# sms_gw.net
KiCad netlist of a schematic drawn in EAGLE
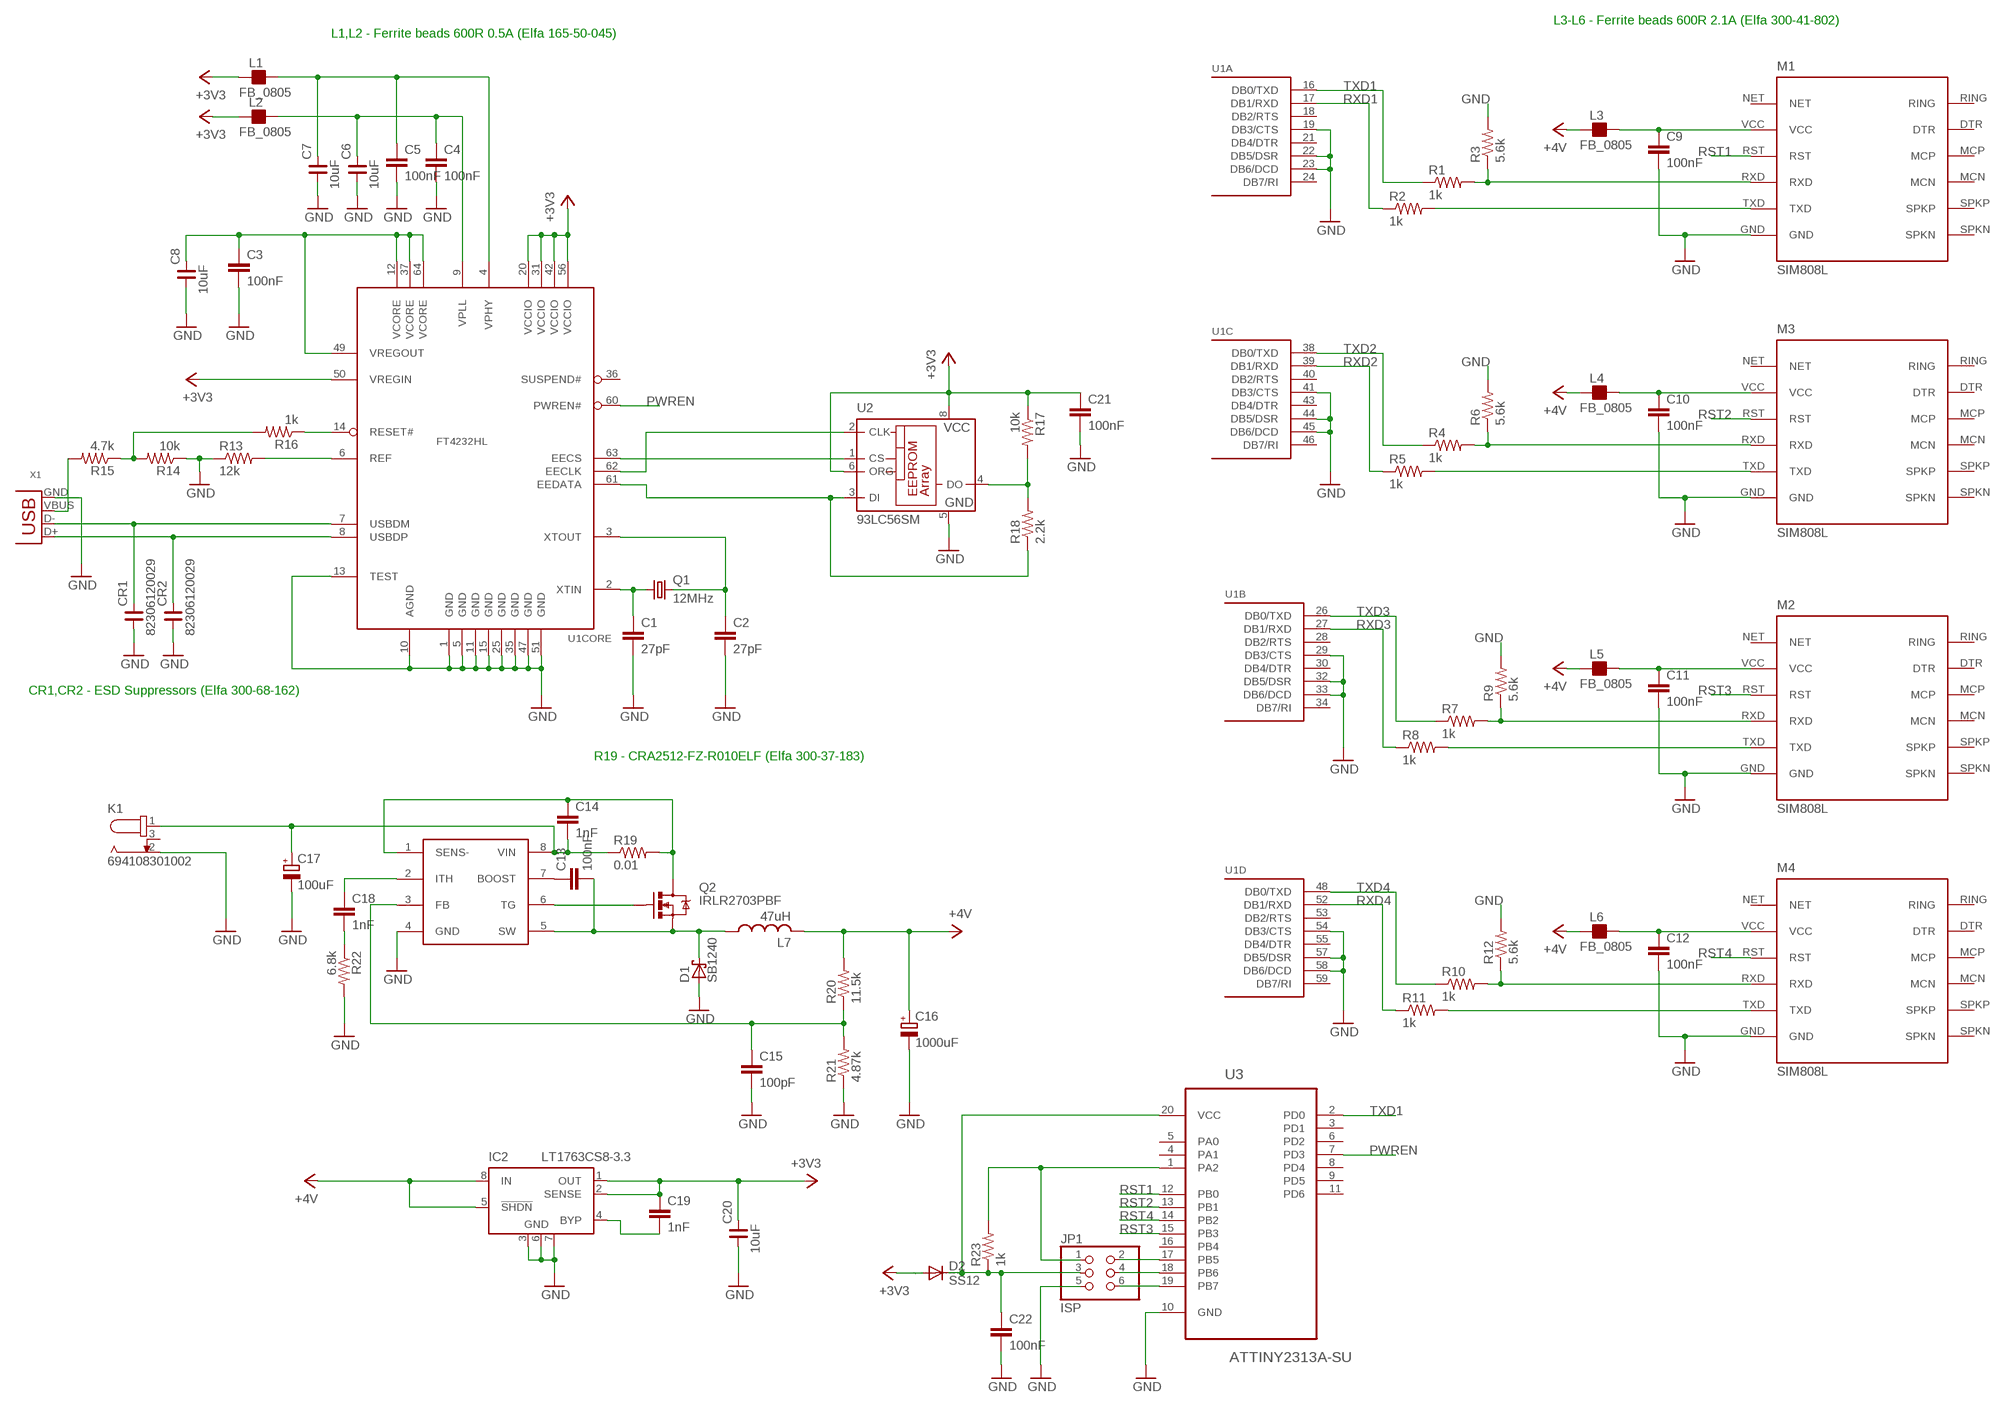
[diagram p0: schematic, sheet 1]

(export (version "E")
  (design (tool "Eeschema 10.0.6"))
  (components
    (comp (ref "C1")
      (value "27pF")
      (footprint "eagle-import:C0805")
      (libsource (lib "eagle-import") (part "C-EUC0805"))
    )
    (comp (ref "C2")
      (value "27pF")
      (footprint "eagle-import:C0805")
      (libsource (lib "eagle-import") (part "C-EUC0805"))
    )
    (comp (ref "C3")
      (value "100nF")
      (footprint "eagle-import:C0805")
      (libsource (lib "eagle-import") (part "C-EUC0805"))
    )
    (comp (ref "C4")
      (value "100nF")
      (footprint "eagle-import:C0805")
      (libsource (lib "eagle-import") (part "C-EUC0805"))
    )
    (comp (ref "C5")
      (value "100nF")
      (footprint "eagle-import:C0805")
      (libsource (lib "eagle-import") (part "C-EUC0805"))
    )
    (comp (ref "C6")
      (value "10uF")
      (footprint "eagle-import:C1210")
      (libsource (lib "eagle-import") (part "C_1210"))
    )
    (comp (ref "C7")
      (value "10uF")
      (footprint "eagle-import:C1210")
      (libsource (lib "eagle-import") (part "C_1210"))
    )
    (comp (ref "C8")
      (value "10uF")
      (footprint "eagle-import:C1210")
      (libsource (lib "eagle-import") (part "C_1210"))
    )
    (comp (ref "C9")
      (value "100nF")
      (footprint "eagle-import:C0805")
      (libsource (lib "eagle-import") (part "C-EUC0805"))
    )
    (comp (ref "C10")
      (value "100nF")
      (footprint "eagle-import:C0805")
      (libsource (lib "eagle-import") (part "C-EUC0805"))
    )
    (comp (ref "C11")
      (value "100nF")
      (footprint "eagle-import:C0805")
      (libsource (lib "eagle-import") (part "C-EUC0805"))
    )
    (comp (ref "C12")
      (value "100nF")
      (footprint "eagle-import:C0805")
      (libsource (lib "eagle-import") (part "C-EUC0805"))
    )
    (comp (ref "C13")
      (value "100nF")
      (footprint "eagle-import:C1206")
      (libsource (lib "eagle-import") (part "C-EUC1206"))
    )
    (comp (ref "C14")
      (value "1nF")
      (footprint "eagle-import:C0805")
      (libsource (lib "eagle-import") (part "C-EUC0805"))
    )
    (comp (ref "C15")
      (value "100pF")
      (footprint "eagle-import:C0805")
      (libsource (lib "eagle-import") (part "C-EUC0805"))
    )
    (comp (ref "C16")
      (value "1000uF")
      (footprint "eagle-import:E5-8,5")
      (libsource (lib "eagle-import") (part "CPOL-EUE5-8.5"))
    )
    (comp (ref "C17")
      (value "100uF")
      (footprint "eagle-import:E5-8,5")
      (libsource (lib "eagle-import") (part "CPOL-EUE5-8.5"))
    )
    (comp (ref "C18")
      (value "1nF")
      (footprint "eagle-import:C0805")
      (libsource (lib "eagle-import") (part "C-EUC0805"))
    )
    (comp (ref "C19")
      (value "1nF")
      (footprint "eagle-import:C0805")
      (libsource (lib "eagle-import") (part "C-EUC0805"))
    )
    (comp (ref "C20")
      (value "10uF")
      (footprint "eagle-import:C1210")
      (libsource (lib "eagle-import") (part "C_1210"))
    )
    (comp (ref "C21")
      (value "100nF")
      (footprint "eagle-import:C0805")
      (libsource (lib "eagle-import") (part "C-EUC0805"))
    )
    (comp (ref "C22")
      (value "100nF")
      (footprint "eagle-import:C0805")
      (libsource (lib "eagle-import") (part "C-EUC0805"))
    )
    (comp (ref "CR1")
      (value "82306120029")
      (footprint "eagle-import:C0603")
      (libsource (lib "eagle-import") (part "C_0603"))
    )
    (comp (ref "CR2")
      (value "82306120029")
      (footprint "eagle-import:C0603")
      (libsource (lib "eagle-import") (part "C_0603"))
    )
    (comp (ref "D1")
      (value "SB1240")
      (footprint "eagle-import:F126Z12")
      (libsource (lib "eagle-import") (part "SCHOTTKY-DIODEF126Z12"))
    )
    (comp (ref "D2")
      (value "SS12")
      (footprint "eagle-import:DO-214AC")
      (libsource (lib "eagle-import") (part "DIODE-DO-214AC"))
    )
    (comp (ref "IC1")
      (value "LTC1624S8")
      (footprint "eagle-import:SO08")
      (libsource (lib "eagle-import") (part "LTC1624S8"))
    )
    (comp (ref "IC2")
      (value "LT1763CS8-3.3")
      (footprint "eagle-import:SOIC8")
      (libsource (lib "eagle-import") (part "LT1763CS8-3.3"))
    )
    (comp (ref "JP1")
      (value "ISP")
      (footprint "eagle-import:2X03")
      (libsource (lib "eagle-import") (part "PINHD-2X3"))
    )
    (comp (ref "K1")
      (value "694108301002")
      (footprint "eagle-import:694108301002")
      (libsource (lib "eagle-import") (part "694108301002"))
    )
    (comp (ref "L1")
      (value "FB_0805")
      (footprint "eagle-import:L0805")
      (libsource (lib "eagle-import") (part "FB_0805"))
    )
    (comp (ref "L2")
      (value "FB_0805")
      (footprint "eagle-import:L0805")
      (libsource (lib "eagle-import") (part "FB_0805"))
    )
    (comp (ref "L3")
      (value "FB_0805")
      (footprint "eagle-import:L0805")
      (libsource (lib "eagle-import") (part "FB_0805"))
    )
    (comp (ref "L4")
      (value "FB_0805")
      (footprint "eagle-import:L0805")
      (libsource (lib "eagle-import") (part "FB_0805"))
    )
    (comp (ref "L5")
      (value "FB_0805")
      (footprint "eagle-import:L0805")
      (libsource (lib "eagle-import") (part "FB_0805"))
    )
    (comp (ref "L6")
      (value "FB_0805")
      (footprint "eagle-import:L0805")
      (libsource (lib "eagle-import") (part "FB_0805"))
    )
    (comp (ref "L7")
      (value "47uH")
      (footprint "eagle-import:TJ3-U2")
      (libsource (lib "eagle-import") (part "L-USTJ3-U2"))
    )
    (comp (ref "M1")
      (value "SIM808L")
      (footprint "eagle-import:SIM800L")
      (libsource (lib "eagle-import") (part "SIM808L"))
    )
    (comp (ref "M2")
      (value "SIM808L")
      (footprint "eagle-import:SIM800L")
      (libsource (lib "eagle-import") (part "SIM808L"))
    )
    (comp (ref "M3")
      (value "SIM808L")
      (footprint "eagle-import:SIM800L")
      (libsource (lib "eagle-import") (part "SIM808L"))
    )
    (comp (ref "M4")
      (value "SIM808L")
      (footprint "eagle-import:SIM800L")
      (libsource (lib "eagle-import") (part "SIM808L"))
    )
    (comp (ref "Q1")
      (value "12MHz")
      (footprint "eagle-import:HC49U-V")
      (libsource (lib "eagle-import") (part "CRYSTALHC49U-V"))
    )
    (comp (ref "Q2")
      (value "IRLR2703PBF")
      (footprint "eagle-import:DPAK")
      (libsource (lib "eagle-import") (part "MOSFET-NCHANNELFDD8780"))
    )
    (comp (ref "R1")
      (value "1k")
      (footprint "eagle-import:R0805")
      (libsource (lib "eagle-import") (part "R-US_R0805"))
    )
    (comp (ref "R2")
      (value "1k")
      (footprint "eagle-import:R0805")
      (libsource (lib "eagle-import") (part "R-US_R0805"))
    )
    (comp (ref "R3")
      (value "5.6k")
      (footprint "eagle-import:R0805")
      (libsource (lib "eagle-import") (part "R-US_R0805"))
    )
    (comp (ref "R4")
      (value "1k")
      (footprint "eagle-import:R0805")
      (libsource (lib "eagle-import") (part "R-US_R0805"))
    )
    (comp (ref "R5")
      (value "1k")
      (footprint "eagle-import:R0805")
      (libsource (lib "eagle-import") (part "R-US_R0805"))
    )
    (comp (ref "R6")
      (value "5.6k")
      (footprint "eagle-import:R0805")
      (libsource (lib "eagle-import") (part "R-US_R0805"))
    )
    (comp (ref "R7")
      (value "1k")
      (footprint "eagle-import:R0805")
      (libsource (lib "eagle-import") (part "R-US_R0805"))
    )
    (comp (ref "R8")
      (value "1k")
      (footprint "eagle-import:R0805")
      (libsource (lib "eagle-import") (part "R-US_R0805"))
    )
    (comp (ref "R9")
      (value "5.6k")
      (footprint "eagle-import:R0805")
      (libsource (lib "eagle-import") (part "R-US_R0805"))
    )
    (comp (ref "R10")
      (value "1k")
      (footprint "eagle-import:R0805")
      (libsource (lib "eagle-import") (part "R-US_R0805"))
    )
    (comp (ref "R11")
      (value "1k")
      (footprint "eagle-import:R0805")
      (libsource (lib "eagle-import") (part "R-US_R0805"))
    )
    (comp (ref "R12")
      (value "5.6k")
      (footprint "eagle-import:R0805")
      (libsource (lib "eagle-import") (part "R-US_R0805"))
    )
    (comp (ref "R13")
      (value "12k")
      (footprint "eagle-import:R0805")
      (libsource (lib "eagle-import") (part "R-US_R0805"))
    )
    (comp (ref "R14")
      (value "10k")
      (footprint "eagle-import:R0805")
      (libsource (lib "eagle-import") (part "R-US_R0805"))
    )
    (comp (ref "R15")
      (value "4.7k")
      (footprint "eagle-import:R0805")
      (libsource (lib "eagle-import") (part "R-US_R0805"))
    )
    (comp (ref "R16")
      (value "1k")
      (footprint "eagle-import:R0805")
      (libsource (lib "eagle-import") (part "R-US_R0805"))
    )
    (comp (ref "R17")
      (value "10k")
      (footprint "eagle-import:R0805")
      (libsource (lib "eagle-import") (part "R-US_R0805"))
    )
    (comp (ref "R18")
      (value "2.2k")
      (footprint "eagle-import:R0805")
      (libsource (lib "eagle-import") (part "R-US_R0805"))
    )
    (comp (ref "R19")
      (value "0.01")
      (footprint "eagle-import:R2512")
      (libsource (lib "eagle-import") (part "R-US_R2512"))
    )
    (comp (ref "R20")
      (value "11.5k")
      (footprint "eagle-import:R0603")
      (libsource (lib "eagle-import") (part "R-US_R0603"))
    )
    (comp (ref "R21")
      (value "4.87k")
      (footprint "eagle-import:R0603")
      (libsource (lib "eagle-import") (part "R-US_R0603"))
    )
    (comp (ref "R22")
      (value "6.8k")
      (footprint "eagle-import:R0805")
      (libsource (lib "eagle-import") (part "R-US_R0805"))
    )
    (comp (ref "R23")
      (value "1k")
      (footprint "eagle-import:R0805")
      (libsource (lib "eagle-import") (part "R-US_R0805"))
    )
    (comp (ref "U1")
      (value "FT4232HL")
      (footprint "eagle-import:LQFP64")
      (libsource (lib "eagle-import") (part "FT4232HL"))
    )
    (comp (ref "U2")
      (value "93LC56SM")
      (footprint "eagle-import:SO-08M")
      (fields (field (name "MF") "MICROCHIP") (field (name "MPN") "93LC56T/SN"))
      (libsource (lib "eagle-import") (part "93SMLC56"))
    )
    (comp (ref "U3")
      (value "ATTINY2313A-SU")
      (footprint "eagle-import:SOIC127P1032X265-20N")
      (libsource (lib "eagle-import") (part "ATTINY2313A-SU"))
    )
    (comp (ref "X1")
      (value "USB-B-H")
      (footprint "eagle-import:USB-B-H")
      (libsource (lib "eagle-import") (part "USB-B-H"))
    )
  )
  (nets
    (net (code "1") (name "+3V3") (class "Default")
      (node (ref "C19") (pin "1") (pinfunction "1_1") (pintype "passive"))
      (node (ref "C20") (pin "2") (pinfunction "2_2") (pintype "passive"))
      (node (ref "C21") (pin "1") (pinfunction "1_1") (pintype "passive"))
      (node (ref "D2") (pin "A") (pinfunction "A_A") (pintype "passive"))
      (node (ref "IC2") (pin "1") (pinfunction "OUT_1") (pintype "passive"))
      (node (ref "IC2") (pin "2") (pinfunction "SENSE_2") (pintype "input"))
      (node (ref "L1") (pin "1") (pinfunction "1_1") (pintype "passive"))
      (node (ref "L2") (pin "1") (pinfunction "1_1") (pintype "passive"))
      (node (ref "R17") (pin "1") (pinfunction "1_1") (pintype "passive"))
      (node (ref "U1") (pin "20") (pinfunction "VCCIO_20") (pintype "power_in"))
      (node (ref "U1") (pin "31") (pinfunction "VCCIO_31") (pintype "power_in"))
      (node (ref "U1") (pin "42") (pinfunction "VCCIO_42") (pintype "power_in"))
      (node (ref "U1") (pin "50") (pinfunction "VREGIN_50") (pintype "bidirectional"))
      (node (ref "U1") (pin "56") (pinfunction "VCCIO_56") (pintype "power_in"))
      (node (ref "U2") (pin "6") (pinfunction "ORG_6") (pintype "input"))
      (node (ref "U2") (pin "8") (pinfunction "VCC_8") (pintype "power_in"))
    )
    (net (code "2") (name "+4V") (class "Default")
      (node (ref "C16") (pin "+") (pinfunction "+_+") (pintype "passive"))
      (node (ref "IC2") (pin "5") (pinfunction "~{SHDN}_5") (pintype "input"))
      (node (ref "IC2") (pin "8") (pinfunction "IN_8") (pintype "input"))
      (node (ref "L3") (pin "1") (pinfunction "1_1") (pintype "passive"))
      (node (ref "L4") (pin "1") (pinfunction "1_1") (pintype "passive"))
      (node (ref "L5") (pin "1") (pinfunction "1_1") (pintype "passive"))
      (node (ref "L6") (pin "1") (pinfunction "1_1") (pintype "passive"))
      (node (ref "L7") (pin "2") (pinfunction "2_2") (pintype "passive"))
      (node (ref "R20") (pin "2") (pinfunction "2_2") (pintype "passive"))
    )
    (net (code "3") (name "/PWREN") (class "Default")
      (node (ref "U1") (pin "60") (pinfunction "PWREN#_60") (pintype "output"))
      (node (ref "U3") (pin "7") (pinfunction "PD3_7") (pintype "bidirectional"))
    )
    (net (code "4") (name "/RST1") (class "Default")
      (node (ref "M1") (pin "RST") (pinfunction "RST_RST") (pintype "bidirectional"))
      (node (ref "U3") (pin "12") (pinfunction "PB0_12") (pintype "bidirectional"))
    )
    (net (code "5") (name "/RST2") (class "Default")
      (node (ref "M3") (pin "RST") (pinfunction "RST_RST") (pintype "bidirectional"))
      (node (ref "U3") (pin "13") (pinfunction "PB1_13") (pintype "bidirectional"))
    )
    (net (code "6") (name "/RST3") (class "Default")
      (node (ref "M2") (pin "RST") (pinfunction "RST_RST") (pintype "bidirectional"))
      (node (ref "U3") (pin "15") (pinfunction "PB3_15") (pintype "bidirectional"))
    )
    (net (code "7") (name "/RST4") (class "Default")
      (node (ref "M4") (pin "RST") (pinfunction "RST_RST") (pintype "bidirectional"))
      (node (ref "U3") (pin "14") (pinfunction "PB2_14") (pintype "bidirectional"))
    )
    (net (code "8") (name "/RXD1") (class "Default")
      (node (ref "R2") (pin "1") (pinfunction "1_1") (pintype "passive"))
      (node (ref "U1") (pin "17") (pinfunction "DB1/RXD_17") (pintype "bidirectional"))
    )
    (net (code "9") (name "/RXD2") (class "Default")
      (node (ref "R5") (pin "1") (pinfunction "1_1") (pintype "passive"))
      (node (ref "U1") (pin "39") (pinfunction "DB1/RXD_39") (pintype "bidirectional"))
    )
    (net (code "10") (name "/RXD3") (class "Default")
      (node (ref "R8") (pin "1") (pinfunction "1_1") (pintype "passive"))
      (node (ref "U1") (pin "27") (pinfunction "DB1/RXD_27") (pintype "bidirectional"))
    )
    (net (code "11") (name "/RXD4") (class "Default")
      (node (ref "R11") (pin "1") (pinfunction "1_1") (pintype "passive"))
      (node (ref "U1") (pin "52") (pinfunction "DB1/RXD_52") (pintype "bidirectional"))
    )
    (net (code "12") (name "/TXD1") (class "Default")
      (node (ref "R1") (pin "1") (pinfunction "1_1") (pintype "passive"))
      (node (ref "U1") (pin "16") (pinfunction "DB0/TXD_16") (pintype "bidirectional"))
      (node (ref "U3") (pin "2") (pinfunction "PD0_2") (pintype "bidirectional"))
    )
    (net (code "13") (name "/TXD2") (class "Default")
      (node (ref "R4") (pin "1") (pinfunction "1_1") (pintype "passive"))
      (node (ref "U1") (pin "38") (pinfunction "DB0/TXD_38") (pintype "bidirectional"))
    )
    (net (code "14") (name "/TXD3") (class "Default")
      (node (ref "R7") (pin "1") (pinfunction "1_1") (pintype "passive"))
      (node (ref "U1") (pin "26") (pinfunction "DB0/TXD_26") (pintype "bidirectional"))
    )
    (net (code "15") (name "/TXD4") (class "Default")
      (node (ref "R10") (pin "1") (pinfunction "1_1") (pintype "passive"))
      (node (ref "U1") (pin "48") (pinfunction "DB0/TXD_48") (pintype "bidirectional"))
    )
    (net (code "16") (name "GND") (class "Default")
      (node (ref "C1") (pin "2") (pinfunction "2_2") (pintype "passive"))
      (node (ref "C10") (pin "2") (pinfunction "2_2") (pintype "passive"))
      (node (ref "C11") (pin "2") (pinfunction "2_2") (pintype "passive"))
      (node (ref "C12") (pin "2") (pinfunction "2_2") (pintype "passive"))
      (node (ref "C15") (pin "2") (pinfunction "2_2") (pintype "passive"))
      (node (ref "C16") (pin "-") (pinfunction "-_-") (pintype "passive"))
      (node (ref "C17") (pin "-") (pinfunction "-_-") (pintype "passive"))
      (node (ref "C2") (pin "2") (pinfunction "2_2") (pintype "passive"))
      (node (ref "C20") (pin "1") (pinfunction "1_1") (pintype "passive"))
      (node (ref "C21") (pin "2") (pinfunction "2_2") (pintype "passive"))
      (node (ref "C22") (pin "2") (pinfunction "2_2") (pintype "passive"))
      (node (ref "C3") (pin "2") (pinfunction "2_2") (pintype "passive"))
      (node (ref "C4") (pin "2") (pinfunction "2_2") (pintype "passive"))
      (node (ref "C5") (pin "2") (pinfunction "2_2") (pintype "passive"))
      (node (ref "C6") (pin "1") (pinfunction "1_1") (pintype "passive"))
      (node (ref "C7") (pin "1") (pinfunction "1_1") (pintype "passive"))
      (node (ref "C8") (pin "1") (pinfunction "1_1") (pintype "passive"))
      (node (ref "C9") (pin "2") (pinfunction "2_2") (pintype "passive"))
      (node (ref "CR1") (pin "1") (pinfunction "1_1") (pintype "passive"))
      (node (ref "CR2") (pin "1") (pinfunction "1_1") (pintype "passive"))
      (node (ref "D1") (pin "A") (pinfunction "A_A") (pintype "passive"))
      (node (ref "IC1") (pin "4") (pinfunction "GND_4") (pintype "power_in"))
      (node (ref "IC2") (pin "3") (pinfunction "GND_3") (pintype "power_in"))
      (node (ref "IC2") (pin "6") (pinfunction "GND_6") (pintype "power_in"))
      (node (ref "IC2") (pin "7") (pinfunction "GND_7") (pintype "power_in"))
      (node (ref "JP1") (pin "5") (pinfunction "5_5") (pintype "passive"))
      (node (ref "K1") (pin "2") (pinfunction "2_2") (pintype "passive"))
      (node (ref "M1") (pin "GND") (pinfunction "GND_GND") (pintype "power_in"))
      (node (ref "M2") (pin "GND") (pinfunction "GND_GND") (pintype "power_in"))
      (node (ref "M3") (pin "GND") (pinfunction "GND_GND") (pintype "power_in"))
      (node (ref "M4") (pin "GND") (pinfunction "GND_GND") (pintype "power_in"))
      (node (ref "R12") (pin "2") (pinfunction "2_2") (pintype "passive"))
      (node (ref "R13") (pin "1") (pinfunction "1_1") (pintype "passive"))
      (node (ref "R14") (pin "1") (pinfunction "1_1") (pintype "passive"))
      (node (ref "R21") (pin "1") (pinfunction "1_1") (pintype "passive"))
      (node (ref "R22") (pin "2") (pinfunction "2_2") (pintype "passive"))
      (node (ref "R3") (pin "2") (pinfunction "2_2") (pintype "passive"))
      (node (ref "R6") (pin "2") (pinfunction "2_2") (pintype "passive"))
      (node (ref "R9") (pin "2") (pinfunction "2_2") (pintype "passive"))
      (node (ref "U1") (pin "1") (pinfunction "GND_1") (pintype "power_in"))
      (node (ref "U1") (pin "10") (pinfunction "AGND_10") (pintype "power_in"))
      (node (ref "U1") (pin "11") (pinfunction "GND_11") (pintype "power_in"))
      (node (ref "U1") (pin "13") (pinfunction "TEST_13") (pintype "input"))
      (node (ref "U1") (pin "15") (pinfunction "GND_15") (pintype "power_in"))
      (node (ref "U1") (pin "19") (pinfunction "DB3/CTS_19") (pintype "bidirectional"))
      (node (ref "U1") (pin "22") (pinfunction "DB5/DSR_22") (pintype "bidirectional"))
      (node (ref "U1") (pin "23") (pinfunction "DB6/DCD_23") (pintype "bidirectional"))
      (node (ref "U1") (pin "25") (pinfunction "GND_25") (pintype "power_in"))
      (node (ref "U1") (pin "29") (pinfunction "DB3/CTS_29") (pintype "bidirectional"))
      (node (ref "U1") (pin "32") (pinfunction "DB5/DSR_32") (pintype "bidirectional"))
      (node (ref "U1") (pin "33") (pinfunction "DB6/DCD_33") (pintype "bidirectional"))
      (node (ref "U1") (pin "35") (pinfunction "GND_35") (pintype "power_in"))
      (node (ref "U1") (pin "41") (pinfunction "DB3/CTS_41") (pintype "bidirectional"))
      (node (ref "U1") (pin "44") (pinfunction "DB5/DSR_44") (pintype "bidirectional"))
      (node (ref "U1") (pin "45") (pinfunction "DB6/DCD_45") (pintype "bidirectional"))
      (node (ref "U1") (pin "47") (pinfunction "GND_47") (pintype "power_in"))
      (node (ref "U1") (pin "5") (pinfunction "GND_5") (pintype "power_in"))
      (node (ref "U1") (pin "51") (pinfunction "GND_51") (pintype "power_in"))
      (node (ref "U1") (pin "54") (pinfunction "DB3/CTS_54") (pintype "bidirectional"))
      (node (ref "U1") (pin "57") (pinfunction "DB5/DSR_57") (pintype "bidirectional"))
      (node (ref "U1") (pin "58") (pinfunction "DB6/DCD_58") (pintype "bidirectional"))
      (node (ref "U2") (pin "5") (pinfunction "GND_5") (pintype "power_in"))
      (node (ref "U3") (pin "10") (pinfunction "GND_10") (pintype "passive"))
      (node (ref "X1") (pin "GND") (pinfunction "GND_GND") (pintype "bidirectional"))
    )
    (net (code "17") (name "Net-(C9-Pad1)") (class "Default")
      (node (ref "C9") (pin "1") (pinfunction "1_1") (pintype "passive"))
      (node (ref "L3") (pin "2") (pinfunction "2_2") (pintype "passive"))
      (node (ref "M1") (pin "VCC") (pinfunction "VCC_VCC") (pintype "power_in"))
    )
    (net (code "18") (name "Net-(C10-Pad1)") (class "Default")
      (node (ref "C10") (pin "1") (pinfunction "1_1") (pintype "passive"))
      (node (ref "L4") (pin "2") (pinfunction "2_2") (pintype "passive"))
      (node (ref "M3") (pin "VCC") (pinfunction "VCC_VCC") (pintype "power_in"))
    )
    (net (code "19") (name "Net-(C11-Pad1)") (class "Default")
      (node (ref "C11") (pin "1") (pinfunction "1_1") (pintype "passive"))
      (node (ref "L5") (pin "2") (pinfunction "2_2") (pintype "passive"))
      (node (ref "M2") (pin "VCC") (pinfunction "VCC_VCC") (pintype "power_in"))
    )
    (net (code "20") (name "Net-(C12-Pad1)") (class "Default")
      (node (ref "C12") (pin "1") (pinfunction "1_1") (pintype "passive"))
      (node (ref "L6") (pin "2") (pinfunction "2_2") (pintype "passive"))
      (node (ref "M4") (pin "VCC") (pinfunction "VCC_VCC") (pintype "power_in"))
    )
    (net (code "21") (name "Net-(C18-Pad2)") (class "Default")
      (node (ref "C18") (pin "2") (pinfunction "2_2") (pintype "passive"))
      (node (ref "R22") (pin "1") (pinfunction "1_1") (pintype "passive"))
    )
    (net (code "22") (name "Net-(IC1-BOOST)") (class "Default")
      (node (ref "C13") (pin "1") (pinfunction "1_1") (pintype "passive"))
      (node (ref "IC1") (pin "7") (pinfunction "BOOST_7") (pintype "bidirectional"))
    )
    (net (code "23") (name "Net-(IC1-FB)") (class "Default")
      (node (ref "C15") (pin "1") (pinfunction "1_1") (pintype "passive"))
      (node (ref "IC1") (pin "3") (pinfunction "FB_3") (pintype "bidirectional"))
      (node (ref "R20") (pin "1") (pinfunction "1_1") (pintype "passive"))
      (node (ref "R21") (pin "2") (pinfunction "2_2") (pintype "passive"))
    )
    (net (code "24") (name "Net-(IC1-ITH)") (class "Default")
      (node (ref "C18") (pin "1") (pinfunction "1_1") (pintype "passive"))
      (node (ref "IC1") (pin "2") (pinfunction "ITH_2") (pintype "bidirectional"))
    )
    (net (code "25") (name "Net-(IC1-SENS-)") (class "Default")
      (node (ref "C14") (pin "1") (pinfunction "1_1") (pintype "passive"))
      (node (ref "IC1") (pin "1") (pinfunction "SENS-_1") (pintype "bidirectional"))
      (node (ref "Q2") (pin "4") (pinfunction "D_4") (pintype "passive"))
      (node (ref "R19") (pin "2") (pinfunction "2_2") (pintype "passive"))
    )
    (net (code "26") (name "Net-(IC1-SW)") (class "Default")
      (node (ref "C13") (pin "2") (pinfunction "2_2") (pintype "passive"))
      (node (ref "D1") (pin "C") (pinfunction "C_C") (pintype "passive"))
      (node (ref "IC1") (pin "5") (pinfunction "SW_5") (pintype "bidirectional"))
      (node (ref "L7") (pin "1") (pinfunction "1_1") (pintype "passive"))
      (node (ref "Q2") (pin "3") (pinfunction "S_3") (pintype "passive"))
    )
    (net (code "27") (name "Net-(IC1-TG)") (class "Default")
      (node (ref "IC1") (pin "6") (pinfunction "TG_6") (pintype "bidirectional"))
      (node (ref "Q2") (pin "1") (pinfunction "G_1") (pintype "passive"))
    )
    (net (code "28") (name "Net-(IC1-VIN)") (class "Default")
      (node (ref "C14") (pin "2") (pinfunction "2_2") (pintype "passive"))
      (node (ref "C17") (pin "+") (pinfunction "+_+") (pintype "passive"))
      (node (ref "IC1") (pin "8") (pinfunction "VIN_8") (pintype "input"))
      (node (ref "K1") (pin "1") (pinfunction "1_1") (pintype "passive"))
      (node (ref "R19") (pin "1") (pinfunction "1_1") (pintype "passive"))
    )
    (net (code "29") (name "Net-(IC2-BYP)") (class "Default")
      (node (ref "C19") (pin "2") (pinfunction "2_2") (pintype "passive"))
      (node (ref "IC2") (pin "4") (pinfunction "BYP_4") (pintype "input"))
    )
    (net (code "30") (name "Net-(M1-PadRXD)") (class "Default")
      (node (ref "M1") (pin "RXD") (pinfunction "RXD_RXD") (pintype "input"))
      (node (ref "R1") (pin "2") (pinfunction "2_2") (pintype "passive"))
      (node (ref "R3") (pin "1") (pinfunction "1_1") (pintype "passive"))
    )
    (net (code "31") (name "Net-(M1-PadTXD)") (class "Default")
      (node (ref "M1") (pin "TXD") (pinfunction "TXD_TXD") (pintype "output"))
      (node (ref "R2") (pin "2") (pinfunction "2_2") (pintype "passive"))
    )
    (net (code "32") (name "Net-(M2-PadRXD)") (class "Default")
      (node (ref "M2") (pin "RXD") (pinfunction "RXD_RXD") (pintype "input"))
      (node (ref "R7") (pin "2") (pinfunction "2_2") (pintype "passive"))
      (node (ref "R9") (pin "1") (pinfunction "1_1") (pintype "passive"))
    )
    (net (code "33") (name "Net-(M2-PadTXD)") (class "Default")
      (node (ref "M2") (pin "TXD") (pinfunction "TXD_TXD") (pintype "output"))
      (node (ref "R8") (pin "2") (pinfunction "2_2") (pintype "passive"))
    )
    (net (code "34") (name "Net-(M3-PadRXD)") (class "Default")
      (node (ref "M3") (pin "RXD") (pinfunction "RXD_RXD") (pintype "input"))
      (node (ref "R4") (pin "2") (pinfunction "2_2") (pintype "passive"))
      (node (ref "R6") (pin "1") (pinfunction "1_1") (pintype "passive"))
    )
    (net (code "35") (name "Net-(M3-PadTXD)") (class "Default")
      (node (ref "M3") (pin "TXD") (pinfunction "TXD_TXD") (pintype "output"))
      (node (ref "R5") (pin "2") (pinfunction "2_2") (pintype "passive"))
    )
    (net (code "36") (name "Net-(M4-PadRXD)") (class "Default")
      (node (ref "M4") (pin "RXD") (pinfunction "RXD_RXD") (pintype "input"))
      (node (ref "R10") (pin "2") (pinfunction "2_2") (pintype "passive"))
      (node (ref "R12") (pin "1") (pinfunction "1_1") (pintype "passive"))
    )
    (net (code "37") (name "Net-(M4-PadTXD)") (class "Default")
      (node (ref "M4") (pin "TXD") (pinfunction "TXD_TXD") (pintype "output"))
      (node (ref "R11") (pin "2") (pinfunction "2_2") (pintype "passive"))
    )
    (net (code "38") (name "Net-(R14-Pad2)") (class "Default")
      (node (ref "R14") (pin "2") (pinfunction "2_2") (pintype "passive"))
      (node (ref "R15") (pin "1") (pinfunction "1_1") (pintype "passive"))
      (node (ref "R16") (pin "2") (pinfunction "2_2") (pintype "passive"))
    )
    (net (code "39") (name "Net-(R15-Pad2)") (class "Default")
      (node (ref "R15") (pin "2") (pinfunction "2_2") (pintype "passive"))
      (node (ref "X1") (pin "VBUS") (pinfunction "VBUS_VBUS") (pintype "bidirectional"))
    )
    (net (code "40") (name "Net-(U1D-EECLK)") (class "Default")
      (node (ref "U1") (pin "62") (pinfunction "EECLK_62") (pintype "output"))
      (node (ref "U2") (pin "2") (pinfunction "CLK_2") (pintype "input"))
    )
    (net (code "41") (name "Net-(U1D-EECS)") (class "Default")
      (node (ref "U1") (pin "63") (pinfunction "EECS_63") (pintype "bidirectional"))
      (node (ref "U2") (pin "1") (pinfunction "CS_1") (pintype "input"))
    )
    (net (code "42") (name "Net-(U1D-EEDATA)") (class "Default")
      (node (ref "R18") (pin "1") (pinfunction "1_1") (pintype "passive"))
      (node (ref "U1") (pin "61") (pinfunction "EEDATA_61") (pintype "bidirectional"))
      (node (ref "U2") (pin "3") (pinfunction "DI_3") (pintype "input"))
    )
    (net (code "43") (name "Net-(U1D-REF)") (class "Default")
      (node (ref "R13") (pin "2") (pinfunction "2_2") (pintype "passive"))
      (node (ref "U1") (pin "6") (pinfunction "REF_6") (pintype "input"))
    )
    (net (code "44") (name "Net-(U1D-RESET#)") (class "Default")
      (node (ref "R16") (pin "1") (pinfunction "1_1") (pintype "passive"))
      (node (ref "U1") (pin "14") (pinfunction "RESET#_14") (pintype "input"))
    )
    (net (code "45") (name "Net-(U1D-USBDM)") (class "Default")
      (node (ref "CR1") (pin "2") (pinfunction "2_2") (pintype "passive"))
      (node (ref "U1") (pin "7") (pinfunction "USBDM_7") (pintype "input"))
      (node (ref "X1") (pin "D-") (pinfunction "D-_D-") (pintype "bidirectional"))
    )
    (net (code "46") (name "Net-(U1D-USBDP)") (class "Default")
      (node (ref "CR2") (pin "2") (pinfunction "2_2") (pintype "passive"))
      (node (ref "U1") (pin "8") (pinfunction "USBDP_8") (pintype "input"))
      (node (ref "X1") (pin "D+") (pinfunction "D+_D+") (pintype "bidirectional"))
    )
    (net (code "47") (name "Net-(U1D-VPHY)") (class "Default")
      (node (ref "C5") (pin "1") (pinfunction "1_1") (pintype "passive"))
      (node (ref "C7") (pin "2") (pinfunction "2_2") (pintype "passive"))
      (node (ref "L1") (pin "2") (pinfunction "2_2") (pintype "passive"))
      (node (ref "U1") (pin "4") (pinfunction "VPHY_4") (pintype "power_in"))
    )
    (net (code "48") (name "Net-(U1D-VPLL)") (class "Default")
      (node (ref "C4") (pin "1") (pinfunction "1_1") (pintype "passive"))
      (node (ref "C6") (pin "2") (pinfunction "2_2") (pintype "passive"))
      (node (ref "L2") (pin "2") (pinfunction "2_2") (pintype "passive"))
      (node (ref "U1") (pin "9") (pinfunction "VPLL_9") (pintype "power_in"))
    )
    (net (code "49") (name "Net-(U1D-VREGOUT)") (class "Default")
      (node (ref "C3") (pin "1") (pinfunction "1_1") (pintype "passive"))
      (node (ref "C8") (pin "2") (pinfunction "2_2") (pintype "passive"))
      (node (ref "U1") (pin "12") (pinfunction "VCORE_12") (pintype "power_in"))
      (node (ref "U1") (pin "37") (pinfunction "VCORE_37") (pintype "power_in"))
      (node (ref "U1") (pin "49") (pinfunction "VREGOUT_49") (pintype "output"))
      (node (ref "U1") (pin "64") (pinfunction "VCORE_64") (pintype "power_in"))
    )
    (net (code "50") (name "Net-(U1D-XTIN)") (class "Default")
      (node (ref "C1") (pin "1") (pinfunction "1_1") (pintype "passive"))
      (node (ref "Q1") (pin "1") (pinfunction "1_1") (pintype "passive"))
      (node (ref "U1") (pin "2") (pinfunction "XTIN_2") (pintype "input"))
    )
    (net (code "51") (name "Net-(U1D-XTOUT)") (class "Default")
      (node (ref "C2") (pin "1") (pinfunction "1_1") (pintype "passive"))
      (node (ref "Q1") (pin "2") (pinfunction "2_2") (pintype "passive"))
      (node (ref "U1") (pin "3") (pinfunction "XTOUT_3") (pintype "output"))
    )
    (net (code "52") (name "Net-(U2-DO)") (class "Default")
      (node (ref "R17") (pin "2") (pinfunction "2_2") (pintype "passive"))
      (node (ref "R18") (pin "2") (pinfunction "2_2") (pintype "passive"))
      (node (ref "U2") (pin "4") (pinfunction "DO_4") (pintype "tri_state"))
    )
    (net (code "53") (name "Net-(U3-PA2)") (class "Default")
      (node (ref "JP1") (pin "1") (pinfunction "1_1") (pintype "passive"))
      (node (ref "R23") (pin "2") (pinfunction "2_2") (pintype "passive"))
      (node (ref "U3") (pin "1") (pinfunction "PA2_1") (pintype "bidirectional"))
    )
    (net (code "54") (name "Net-(U3-PB5)") (class "Default")
      (node (ref "JP1") (pin "2") (pinfunction "2_2") (pintype "passive"))
      (node (ref "U3") (pin "17") (pinfunction "PB5_17") (pintype "bidirectional"))
    )
    (net (code "55") (name "Net-(U3-PB6)") (class "Default")
      (node (ref "JP1") (pin "4") (pinfunction "4_4") (pintype "passive"))
      (node (ref "U3") (pin "18") (pinfunction "PB6_18") (pintype "bidirectional"))
    )
    (net (code "56") (name "Net-(U3-PB7)") (class "Default")
      (node (ref "JP1") (pin "6") (pinfunction "6_6") (pintype "passive"))
      (node (ref "U3") (pin "19") (pinfunction "PB7_19") (pintype "bidirectional"))
    )
    (net (code "57") (name "Net-(U3-VCC)") (class "Default")
      (node (ref "C22") (pin "1") (pinfunction "1_1") (pintype "passive"))
      (node (ref "D2") (pin "C") (pinfunction "C_C") (pintype "passive"))
      (node (ref "JP1") (pin "3") (pinfunction "3_3") (pintype "passive"))
      (node (ref "R23") (pin "1") (pinfunction "1_1") (pintype "passive"))
      (node (ref "U3") (pin "20") (pinfunction "VCC_20") (pintype "power_in"))
    )
    (net (code "58") (name "unconnected-(K1-Pad3)") (class "Default")
      (node (ref "K1") (pin "3") (pinfunction "3_3") (pintype "passive"))
    )
    (net (code "59") (name "unconnected-(M1-PadDTR)") (class "Default")
      (node (ref "M1") (pin "DTR") (pinfunction "DTR_DTR") (pintype "bidirectional"))
    )
    (net (code "60") (name "unconnected-(M1-PadMCN)") (class "Default")
      (node (ref "M1") (pin "MCN") (pinfunction "MCN_MCN") (pintype "bidirectional"))
    )
    (net (code "61") (name "unconnected-(M1-PadMCP)") (class "Default")
      (node (ref "M1") (pin "MCP") (pinfunction "MCP_MCP") (pintype "bidirectional"))
    )
    (net (code "62") (name "unconnected-(M1-PadNET)") (class "Default")
      (node (ref "M1") (pin "NET") (pinfunction "NET_NET") (pintype "bidirectional"))
    )
    (net (code "63") (name "unconnected-(M1-PadRING)") (class "Default")
      (node (ref "M1") (pin "RING") (pinfunction "RING_RING") (pintype "output"))
    )
    (net (code "64") (name "unconnected-(M1-PadSPKN)") (class "Default")
      (node (ref "M1") (pin "SPKN") (pinfunction "SPKN_SPKN") (pintype "bidirectional"))
    )
    (net (code "65") (name "unconnected-(M1-PadSPKP)") (class "Default")
      (node (ref "M1") (pin "SPKP") (pinfunction "SPKP_SPKP") (pintype "bidirectional"))
    )
    (net (code "66") (name "unconnected-(M2-PadDTR)") (class "Default")
      (node (ref "M2") (pin "DTR") (pinfunction "DTR_DTR") (pintype "bidirectional"))
    )
    (net (code "67") (name "unconnected-(M2-PadMCN)") (class "Default")
      (node (ref "M2") (pin "MCN") (pinfunction "MCN_MCN") (pintype "bidirectional"))
    )
    (net (code "68") (name "unconnected-(M2-PadMCP)") (class "Default")
      (node (ref "M2") (pin "MCP") (pinfunction "MCP_MCP") (pintype "bidirectional"))
    )
    (net (code "69") (name "unconnected-(M2-PadNET)") (class "Default")
      (node (ref "M2") (pin "NET") (pinfunction "NET_NET") (pintype "bidirectional"))
    )
    (net (code "70") (name "unconnected-(M2-PadRING)") (class "Default")
      (node (ref "M2") (pin "RING") (pinfunction "RING_RING") (pintype "output"))
    )
    (net (code "71") (name "unconnected-(M2-PadSPKN)") (class "Default")
      (node (ref "M2") (pin "SPKN") (pinfunction "SPKN_SPKN") (pintype "bidirectional"))
    )
    (net (code "72") (name "unconnected-(M2-PadSPKP)") (class "Default")
      (node (ref "M2") (pin "SPKP") (pinfunction "SPKP_SPKP") (pintype "bidirectional"))
    )
    (net (code "73") (name "unconnected-(M3-PadDTR)") (class "Default")
      (node (ref "M3") (pin "DTR") (pinfunction "DTR_DTR") (pintype "bidirectional"))
    )
    (net (code "74") (name "unconnected-(M3-PadMCN)") (class "Default")
      (node (ref "M3") (pin "MCN") (pinfunction "MCN_MCN") (pintype "bidirectional"))
    )
    (net (code "75") (name "unconnected-(M3-PadMCP)") (class "Default")
      (node (ref "M3") (pin "MCP") (pinfunction "MCP_MCP") (pintype "bidirectional"))
    )
    (net (code "76") (name "unconnected-(M3-PadNET)") (class "Default")
      (node (ref "M3") (pin "NET") (pinfunction "NET_NET") (pintype "bidirectional"))
    )
    (net (code "77") (name "unconnected-(M3-PadRING)") (class "Default")
      (node (ref "M3") (pin "RING") (pinfunction "RING_RING") (pintype "output"))
    )
    (net (code "78") (name "unconnected-(M3-PadSPKN)") (class "Default")
      (node (ref "M3") (pin "SPKN") (pinfunction "SPKN_SPKN") (pintype "bidirectional"))
    )
    (net (code "79") (name "unconnected-(M3-PadSPKP)") (class "Default")
      (node (ref "M3") (pin "SPKP") (pinfunction "SPKP_SPKP") (pintype "bidirectional"))
    )
    (net (code "80") (name "unconnected-(M4-PadDTR)") (class "Default")
      (node (ref "M4") (pin "DTR") (pinfunction "DTR_DTR") (pintype "bidirectional"))
    )
    (net (code "81") (name "unconnected-(M4-PadMCN)") (class "Default")
      (node (ref "M4") (pin "MCN") (pinfunction "MCN_MCN") (pintype "bidirectional"))
    )
    (net (code "82") (name "unconnected-(M4-PadMCP)") (class "Default")
      (node (ref "M4") (pin "MCP") (pinfunction "MCP_MCP") (pintype "bidirectional"))
    )
    (net (code "83") (name "unconnected-(M4-PadNET)") (class "Default")
      (node (ref "M4") (pin "NET") (pinfunction "NET_NET") (pintype "bidirectional"))
    )
    (net (code "84") (name "unconnected-(M4-PadRING)") (class "Default")
      (node (ref "M4") (pin "RING") (pinfunction "RING_RING") (pintype "output"))
    )
    (net (code "85") (name "unconnected-(M4-PadSPKN)") (class "Default")
      (node (ref "M4") (pin "SPKN") (pinfunction "SPKN_SPKN") (pintype "bidirectional"))
    )
    (net (code "86") (name "unconnected-(M4-PadSPKP)") (class "Default")
      (node (ref "M4") (pin "SPKP") (pinfunction "SPKP_SPKP") (pintype "bidirectional"))
    )
    (net (code "87") (name "unconnected-(U1A-DB2{slash}RTS-Pad18)") (class "Default")
      (node (ref "U1") (pin "18") (pinfunction "DB2/RTS_18") (pintype "bidirectional"))
    )
    (net (code "88") (name "unconnected-(U1A-DB4{slash}DTR-Pad21)") (class "Default")
      (node (ref "U1") (pin "21") (pinfunction "DB4/DTR_21") (pintype "bidirectional"))
    )
    (net (code "89") (name "unconnected-(U1A-DB7{slash}RI-Pad24)") (class "Default")
      (node (ref "U1") (pin "24") (pinfunction "DB7/RI_24") (pintype "bidirectional"))
    )
    (net (code "90") (name "unconnected-(U1B-DB2{slash}RTS-Pad28)") (class "Default")
      (node (ref "U1") (pin "28") (pinfunction "DB2/RTS_28") (pintype "bidirectional"))
    )
    (net (code "91") (name "unconnected-(U1B-DB4{slash}DTR-Pad30)") (class "Default")
      (node (ref "U1") (pin "30") (pinfunction "DB4/DTR_30") (pintype "bidirectional"))
    )
    (net (code "92") (name "unconnected-(U1B-DB7{slash}RI-Pad34)") (class "Default")
      (node (ref "U1") (pin "34") (pinfunction "DB7/RI_34") (pintype "bidirectional"))
    )
    (net (code "93") (name "unconnected-(U1C-DB2{slash}RTS-Pad40)") (class "Default")
      (node (ref "U1") (pin "40") (pinfunction "DB2/RTS_40") (pintype "bidirectional"))
    )
    (net (code "94") (name "unconnected-(U1C-DB4{slash}DTR-Pad43)") (class "Default")
      (node (ref "U1") (pin "43") (pinfunction "DB4/DTR_43") (pintype "bidirectional"))
    )
    (net (code "95") (name "unconnected-(U1C-DB7{slash}RI-Pad46)") (class "Default")
      (node (ref "U1") (pin "46") (pinfunction "DB7/RI_46") (pintype "bidirectional"))
    )
    (net (code "96") (name "unconnected-(U1D-SUSPEND#-Pad36)") (class "Default")
      (node (ref "U1") (pin "36") (pinfunction "SUSPEND#_36") (pintype "output"))
    )
    (net (code "97") (name "unconnected-(U1E-DB2{slash}RTS-Pad53)") (class "Default")
      (node (ref "U1") (pin "53") (pinfunction "DB2/RTS_53") (pintype "bidirectional"))
    )
    (net (code "98") (name "unconnected-(U1E-DB4{slash}DTR-Pad55)") (class "Default")
      (node (ref "U1") (pin "55") (pinfunction "DB4/DTR_55") (pintype "bidirectional"))
    )
    (net (code "99") (name "unconnected-(U1E-DB7{slash}RI-Pad59)") (class "Default")
      (node (ref "U1") (pin "59") (pinfunction "DB7/RI_59") (pintype "bidirectional"))
    )
    (net (code "100") (name "unconnected-(U2-NU-Pad7)") (class "Default")
      (node (ref "U2") (pin "7") (pinfunction "NU_7") (pintype "passive"))
    )
    (net (code "101") (name "unconnected-(U3-PA0-Pad5)") (class "Default")
      (node (ref "U3") (pin "5") (pinfunction "PA0_5") (pintype "bidirectional"))
    )
    (net (code "102") (name "unconnected-(U3-PA1-Pad4)") (class "Default")
      (node (ref "U3") (pin "4") (pinfunction "PA1_4") (pintype "bidirectional"))
    )
    (net (code "103") (name "unconnected-(U3-PB4-Pad16)") (class "Default")
      (node (ref "U3") (pin "16") (pinfunction "PB4_16") (pintype "bidirectional"))
    )
    (net (code "104") (name "unconnected-(U3-PD1-Pad3)") (class "Default")
      (node (ref "U3") (pin "3") (pinfunction "PD1_3") (pintype "bidirectional"))
    )
    (net (code "105") (name "unconnected-(U3-PD2-Pad6)") (class "Default")
      (node (ref "U3") (pin "6") (pinfunction "PD2_6") (pintype "bidirectional"))
    )
    (net (code "106") (name "unconnected-(U3-PD4-Pad8)") (class "Default")
      (node (ref "U3") (pin "8") (pinfunction "PD4_8") (pintype "bidirectional"))
    )
    (net (code "107") (name "unconnected-(U3-PD5-Pad9)") (class "Default")
      (node (ref "U3") (pin "9") (pinfunction "PD5_9") (pintype "bidirectional"))
    )
    (net (code "108") (name "unconnected-(U3-PD6-Pad11)") (class "Default")
      (node (ref "U3") (pin "11") (pinfunction "PD6_11") (pintype "bidirectional"))
    )
  )
)
